# AC220V-DC5V_SCH.net
KiCad netlist of a schematic drawn in Altium Designer
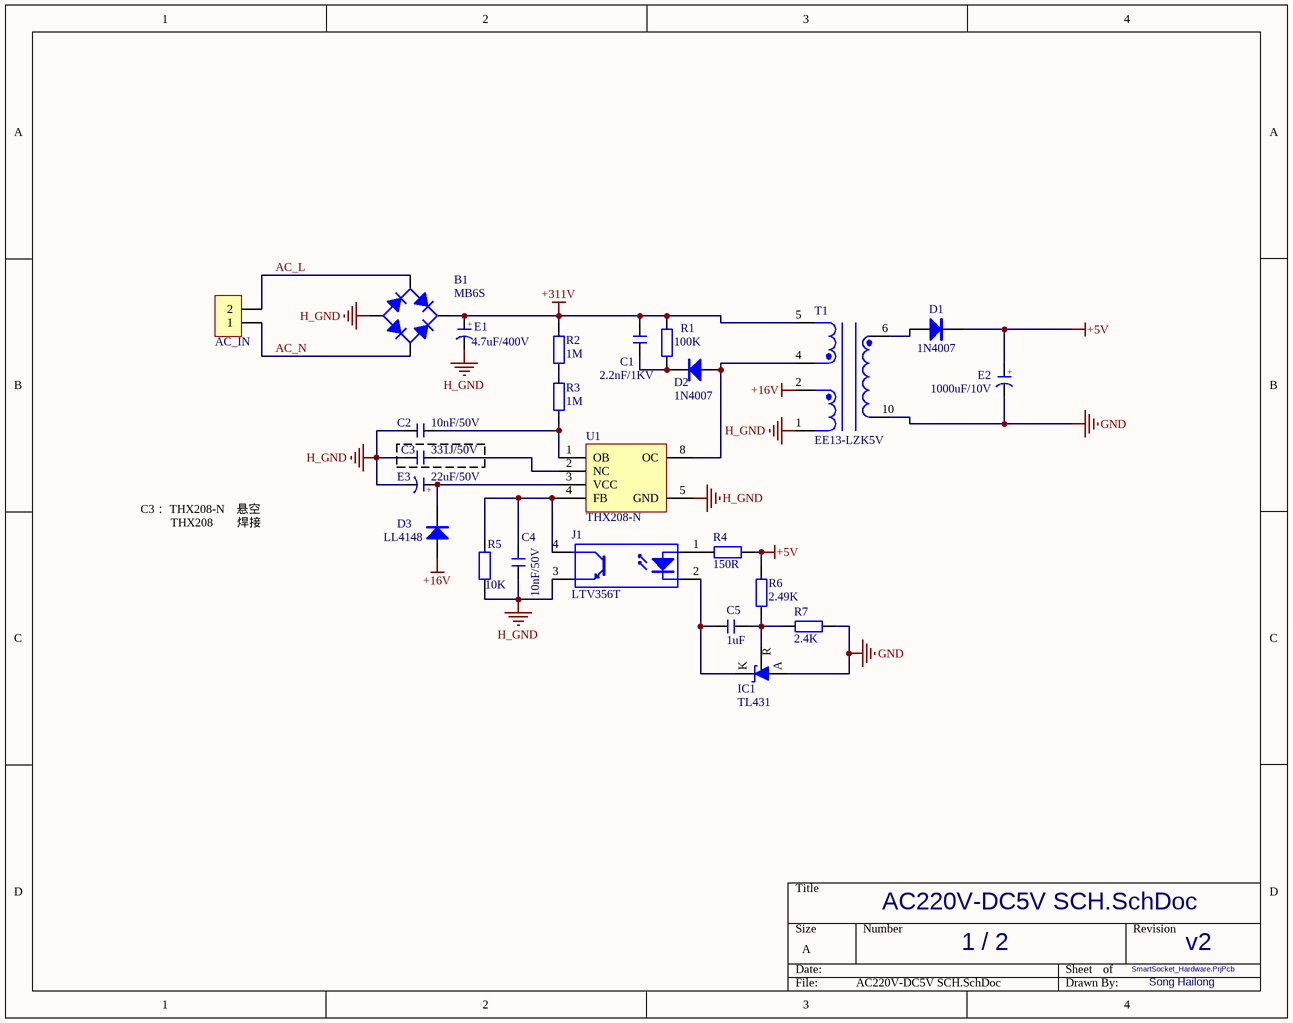
[diagram p0: AC220V-DC5V SCH.SchDoc]

(export (version "E")
  (design (tool "Eeschema 10.0.6"))
  (components
    (comp (ref "AC_IN")
      (value "HDR-1X2")
      (footprint "KF301-5.0-2P")
      (description "2P接插件")
      (fields (field (name "版权归属") "源创客"))
      (libsource (lib "海龍集成库") (part "Header 02 5.0"))
    )
    (comp (ref "B1")
      (value "MB6S")
      (footprint "MBS")
      (description "整流桥")
      (fields (field (name "版权归属") "源创客"))
      (libsource (lib "海龍集成库") (part "DB"))
    )
    (comp (ref "C1")
      (value "2.2nF/1KV")
      (footprint "CBB 5*6.3*3")
      (description "CBB电容")
      (fields (field (name "版权归属") "源创客"))
      (libsource (lib "海龍集成库") (part "C-CBB"))
    )
    (comp (ref "C2")
      (value "10nF/50V")
      (footprint "C 0603_L")
      (description "无极性贴片电容")
      (fields (field (name "版权归属") "源创客"))
      (libsource (lib "海龍集成库") (part "C"))
    )
    (comp (ref "C3")
      (value "331J/50V")
      (footprint "C 0603_L")
      (description "无极性贴片电容")
      (fields (field (name "版权归属") "源创客"))
      (libsource (lib "海龍集成库") (part "C"))
    )
    (comp (ref "C4")
      (value "10nF/50V")
      (footprint "C 0603_L")
      (description "无极性贴片电容")
      (fields (field (name "版权归属") "源创客"))
      (libsource (lib "海龍集成库") (part "C"))
    )
    (comp (ref "C5")
      (value "1uF")
      (footprint "C 0603_L")
      (description "无极性贴片电容")
      (fields (field (name "版权归属") "源创客"))
      (libsource (lib "海龍集成库") (part "C"))
    )
    (comp (ref "D1")
      (value "1N4007")
      (footprint "SMA")
      (description "整流二极管")
      (fields (field (name "版权归属") "源创客"))
      (libsource (lib "海龍集成库") (part "1N4007"))
    )
    (comp (ref "D2")
      (value "1N4007")
      (footprint "SMA")
      (description "整流二极管")
      (fields (field (name "版权归属") "源创客"))
      (libsource (lib "海龍集成库") (part "1N4007"))
    )
    (comp (ref "D3")
      (value "LL4148")
      (footprint "MINI_MELF (LL34)")
      (description "高速开关二极管")
      (fields (field (name "版权归属") "源创客"))
      (libsource (lib "海龍集成库") (part "1N4148"))
    )
    (comp (ref "E1")
      (value "4.7uF/400V")
      (footprint "CAP 2.5*6.3*11.2 - GD")
      (description "直插电解电容")
      (fields (field (name "版权归属") "源创客"))
      (libsource (lib "") (part "C-CAP_1"))
    )
    (comp (ref "E2")
      (value "1000uF/10V")
      (footprint "CAP 3.5*8*11.5")
      (description "直插电解电容")
      (fields (field (name "版权归属") "源创客"))
      (libsource (lib "") (part "C-CAP_1"))
    )
    (comp (ref "E3")
      (value "22uF/50V")
      (footprint "CAP 2.0*5*11")
      (description "直插电解电容")
      (fields (field (name "版权归属") "源创客"))
      (libsource (lib "海龍集成库") (part "C-CAP"))
    )
    (comp (ref "IC1")
      (value "TL431")
      (footprint "SOT23-3M")
      (description "可调基准稳压芯片")
      (fields (field (name "版权归属") "源创客"))
      (libsource (lib "海龍集成库") (part "TL431_SMD"))
    )
    (comp (ref "J1")
      (value "LTV356T")
      (footprint "SOP4_N")
      (description "光耦")
      (fields (field (name "版权归属") "源创客"))
      (libsource (lib "海龍集成库") (part "TLP181"))
    )
    (comp (ref "R1")
      (value "100K")
      (footprint "R 0603_L")
      (description "贴片电阻")
      (fields (field (name "版权归属") "源创客"))
      (libsource (lib "海龍集成库") (part "R"))
    )
    (comp (ref "R2")
      (value "1M")
      (footprint "R 0603_L")
      (description "贴片电阻")
      (fields (field (name "版权归属") "源创客"))
      (libsource (lib "海龍集成库") (part "R"))
    )
    (comp (ref "R3")
      (value "1M")
      (footprint "R 0603_L")
      (description "贴片电阻")
      (fields (field (name "版权归属") "源创客"))
      (libsource (lib "海龍集成库") (part "R"))
    )
    (comp (ref "R4")
      (value "150R")
      (footprint "R 0603_L")
      (description "贴片电阻")
      (fields (field (name "版权归属") "源创客"))
      (libsource (lib "海龍集成库") (part "R"))
    )
    (comp (ref "R5")
      (value "10K")
      (footprint "R 0603_L")
      (description "贴片电阻")
      (fields (field (name "版权归属") "源创客"))
      (libsource (lib "海龍集成库") (part "R"))
    )
    (comp (ref "R6")
      (value "2.49K")
      (footprint "R 0603_L")
      (description "贴片电阻")
      (fields (field (name "版权归属") "源创客"))
      (libsource (lib "海龍集成库") (part "R"))
    )
    (comp (ref "R7")
      (value "2.4K")
      (footprint "R 0603_L")
      (description "贴片电阻")
      (fields (field (name "版权归属") "源创客"))
      (libsource (lib "海龍集成库") (part "R"))
    )
    (comp (ref "T1")
      (value "EE13-LZK5V")
      (footprint "EE13-5V 4+2")
      (description "EE13-LZK5V型 2.50mH立式 高频变压器")
      (libsource (lib "海龍集成库") (part "EE13-LZK5V"))
    )
    (comp (ref "U1")
      (value "THX208-N")
      (footprint "SOP8-6D")
      (description "开关电源芯片")
      (libsource (lib "海龍集成库") (part "THX208-N"))
    )
  )
  (nets
    (net (code "1") (name "+5V") (class "Default")
      (node (ref "D1") (pin "2") (pinfunction "K_2") (pintype "passive"))
      (node (ref "E2") (pin "1") (pinfunction "A_1") (pintype "passive"))
      (node (ref "R4") (pin "1") (pinfunction "1_1") (pintype "passive"))
      (node (ref "R6") (pin "1") (pinfunction "1_1") (pintype "passive"))
    )
    (net (code "2") (name "+16V") (class "Default")
      (node (ref "D3") (pin "1") (pinfunction "A_1") (pintype "passive"))
      (node (ref "T1") (pin "2") (pinfunction "2_2") (pintype "passive"))
    )
    (net (code "3") (name "+311V") (class "Default")
      (node (ref "B1") (pin "DC+") (pinfunction "DC+_DC+") (pintype "passive"))
      (node (ref "C1") (pin "2") (pinfunction "2_2") (pintype "passive"))
      (node (ref "E1") (pin "1") (pinfunction "A_1") (pintype "passive"))
      (node (ref "R1") (pin "1") (pinfunction "1_1") (pintype "passive"))
      (node (ref "R2") (pin "1") (pinfunction "1_1") (pintype "passive"))
      (node (ref "T1") (pin "5") (pinfunction "5_5") (pintype "passive"))
    )
    (net (code "4") (name "/AC_L") (class "Default")
      (node (ref "AC_IN") (pin "2") (pinfunction "2_2") (pintype "passive"))
      (node (ref "B1") (pin "AC1") (pinfunction "AC1_AC1") (pintype "passive"))
    )
    (net (code "5") (name "/AC_N") (class "Default")
      (node (ref "AC_IN") (pin "1") (pinfunction "1_1") (pintype "passive"))
      (node (ref "B1") (pin "AC2") (pinfunction "AC2_AC2") (pintype "passive"))
    )
    (net (code "6") (name "GND") (class "Default")
      (node (ref "E2") (pin "2") (pinfunction "K_2") (pintype "passive"))
      (node (ref "IC1") (pin "3") (pinfunction "A_3") (pintype "passive"))
      (node (ref "R7") (pin "2") (pinfunction "2_2") (pintype "passive"))
      (node (ref "T1") (pin "10") (pinfunction "10_10") (pintype "passive"))
    )
    (net (code "7") (name "H_GND") (class "Default")
      (node (ref "B1") (pin "DC-") (pinfunction "DC-_DC-") (pintype "passive"))
      (node (ref "C2") (pin "2") (pinfunction "2_2") (pintype "passive"))
      (node (ref "C3") (pin "2") (pinfunction "2_2") (pintype "passive"))
      (node (ref "C4") (pin "2") (pinfunction "2_2") (pintype "passive"))
      (node (ref "E1") (pin "2") (pinfunction "K_2") (pintype "passive"))
      (node (ref "E3") (pin "2") (pinfunction "K_2") (pintype "passive"))
      (node (ref "J1") (pin "3") (pinfunction "E_3") (pintype "passive"))
      (node (ref "R5") (pin "1") (pinfunction "1_1") (pintype "passive"))
      (node (ref "T1") (pin "1") (pinfunction "1_1") (pintype "passive"))
      (node (ref "U1") (pin "5") (pinfunction "GND_5") (pintype "power_in"))
    )
    (net (code "8") (name "Net-(D1-A)") (class "Default")
      (node (ref "D1") (pin "1") (pinfunction "A_1") (pintype "passive"))
      (node (ref "T1") (pin "6") (pinfunction "6_6") (pintype "passive"))
    )
    (net (code "9") (name "Net-(D2-A)") (class "Default")
      (node (ref "D2") (pin "1") (pinfunction "A_1") (pintype "passive"))
      (node (ref "T1") (pin "4") (pinfunction "4_4") (pintype "passive"))
      (node (ref "U1") (pin "8") (pinfunction "OC_8") (pintype "power_in"))
    )
    (net (code "10") (name "Net-(D2-K)") (class "Default")
      (node (ref "C1") (pin "1") (pinfunction "1_1") (pintype "passive"))
      (node (ref "D2") (pin "2") (pinfunction "K_2") (pintype "passive"))
      (node (ref "R1") (pin "2") (pinfunction "2_2") (pintype "passive"))
    )
    (net (code "11") (name "Net-(D3-K)") (class "Default")
      (node (ref "D3") (pin "2") (pinfunction "K_2") (pintype "passive"))
      (node (ref "E3") (pin "1") (pinfunction "A_1") (pintype "passive"))
      (node (ref "U1") (pin "3") (pinfunction "VCC_3") (pintype "power_in"))
    )
    (net (code "12") (name "Net-(IC1-K)") (class "Default")
      (node (ref "C5") (pin "1") (pinfunction "1_1") (pintype "passive"))
      (node (ref "IC1") (pin "2") (pinfunction "K_2") (pintype "passive"))
      (node (ref "J1") (pin "2") (pinfunction "K_2") (pintype "passive"))
    )
    (net (code "13") (name "Net-(IC1-R)") (class "Default")
      (node (ref "C5") (pin "2") (pinfunction "2_2") (pintype "passive"))
      (node (ref "IC1") (pin "1") (pinfunction "R_1") (pintype "passive"))
      (node (ref "R6") (pin "2") (pinfunction "2_2") (pintype "passive"))
      (node (ref "R7") (pin "1") (pinfunction "1_1") (pintype "passive"))
    )
    (net (code "14") (name "Net-(J1-A)") (class "Default")
      (node (ref "J1") (pin "1") (pinfunction "A_1") (pintype "passive"))
      (node (ref "R4") (pin "2") (pinfunction "2_2") (pintype "passive"))
    )
    (net (code "15") (name "Net-(J1-C)") (class "Default")
      (node (ref "C4") (pin "1") (pinfunction "1_1") (pintype "passive"))
      (node (ref "J1") (pin "4") (pinfunction "C_4") (pintype "passive"))
      (node (ref "R5") (pin "2") (pinfunction "2_2") (pintype "passive"))
      (node (ref "U1") (pin "4") (pinfunction "FB_4") (pintype "power_in"))
    )
    (net (code "16") (name "Net-(R2-Pad2)") (class "Default")
      (node (ref "R2") (pin "2") (pinfunction "2_2") (pintype "passive"))
      (node (ref "R3") (pin "1") (pinfunction "1_1") (pintype "passive"))
    )
    (net (code "17") (name "Net-(U1-NC)") (class "Default")
      (node (ref "C3") (pin "1") (pinfunction "1_1") (pintype "passive"))
      (node (ref "U1") (pin "2") (pinfunction "NC_2") (pintype "power_in"))
    )
    (net (code "18") (name "Net-(U1-OB)") (class "Default")
      (node (ref "C2") (pin "1") (pinfunction "1_1") (pintype "passive"))
      (node (ref "R3") (pin "2") (pinfunction "2_2") (pintype "passive"))
      (node (ref "U1") (pin "1") (pinfunction "OB_1") (pintype "power_in"))
    )
  )
)
